# Bluetooth.net
KiCad netlist of a schematic drawn in Altium Designer
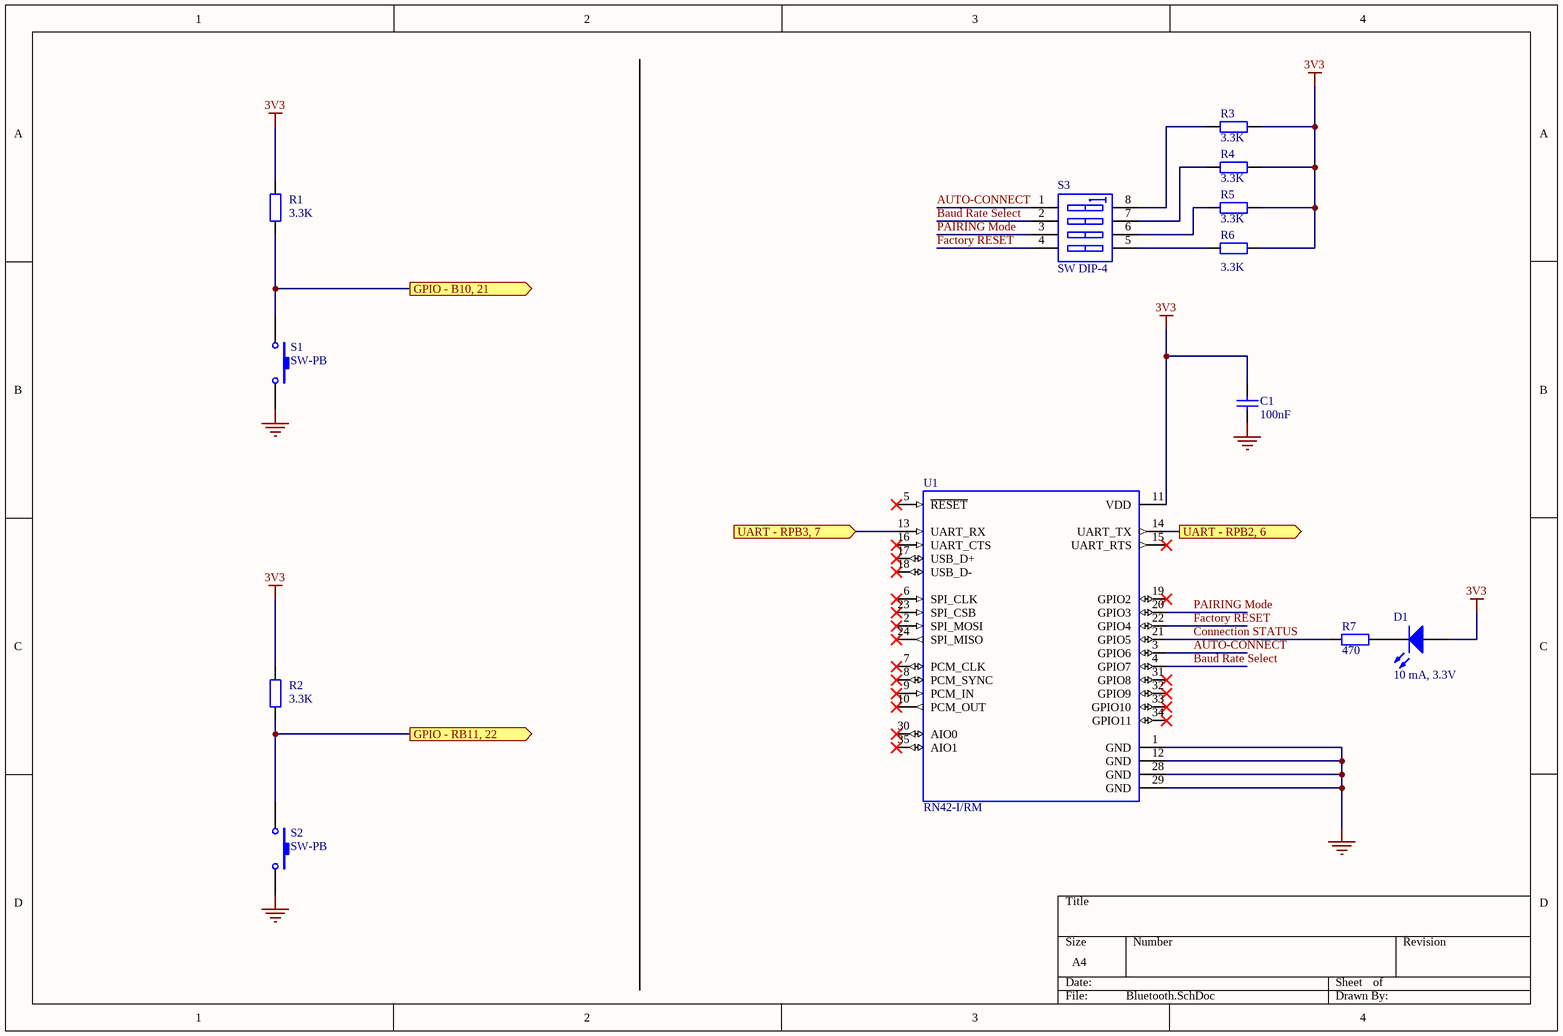
[diagram p0: Bluetooth.SchDoc]

(export (version "E")
  (design (tool "Eeschema 10.0.6"))
  (components
    (comp (ref "C1")
      (value "100nF")
      (footprint "RAD-0.3")
      (description "Capacitor")
      (fields (field (name "PUBLISHER") "Altium Limited"))
      (libsource (lib "Miscellaneous Devices") (part "Cap"))
    )
    (comp (ref "D1")
      (value "10 mA, 3.3V")
      (footprint "LED-0")
      (description "Typical INFRARED GaAs LED")
      (fields (field (name "PUBLISHER") "Altium Limited"))
      (libsource (lib "Miscellaneous Devices") (part "LED0"))
    )
    (comp (ref "R1")
      (value "3.3K")
      (footprint "AXIAL-0.4")
      (description "Resistor")
      (fields (field (name "PUBLISHER") "Altium Limited"))
      (libsource (lib "") (part "Res2_1"))
    )
    (comp (ref "R2")
      (value "3.3K")
      (footprint "AXIAL-0.4")
      (description "Resistor")
      (fields (field (name "PUBLISHER") "Altium Limited"))
      (libsource (lib "") (part "Res2_1"))
    )
    (comp (ref "R3")
      (value "3.3K")
      (footprint "AXIAL-0.4")
      (description "Resistor")
      (fields (field (name "PUBLISHER") "Altium Limited"))
      (libsource (lib "Miscellaneous Devices") (part "Res2"))
    )
    (comp (ref "R4")
      (value "3.3K")
      (footprint "AXIAL-0.4")
      (description "Resistor")
      (fields (field (name "PUBLISHER") "Altium Limited"))
      (libsource (lib "Miscellaneous Devices") (part "Res2"))
    )
    (comp (ref "R5")
      (value "3.3K")
      (footprint "AXIAL-0.4")
      (description "Resistor")
      (fields (field (name "PUBLISHER") "Altium Limited"))
      (libsource (lib "Miscellaneous Devices") (part "Res2"))
    )
    (comp (ref "R6")
      (value "3.3K")
      (footprint "AXIAL-0.4")
      (description "Resistor")
      (fields (field (name "PUBLISHER") "Altium Limited"))
      (libsource (lib "Miscellaneous Devices") (part "Res2"))
    )
    (comp (ref "R7")
      (value "470")
      (footprint "AXIAL-0.4")
      (description "Resistor")
      (fields (field (name "PUBLISHER") "Altium Limited"))
      (libsource (lib "Miscellaneous Devices") (part "Res2"))
    )
    (comp (ref "S1")
      (value "SW-PB")
      (footprint "SPST-2")
      (description "Switch")
      (fields (field (name "PUBLISHER") "Altium Limited"))
      (libsource (lib "Miscellaneous Devices") (part "SW-PB"))
    )
    (comp (ref "S2")
      (value "SW-PB")
      (footprint "SPST-2")
      (description "Switch")
      (fields (field (name "PUBLISHER") "Altium Limited"))
      (libsource (lib "Miscellaneous Devices") (part "SW-PB"))
    )
    (comp (ref "S3")
      (value "SW DIP-4")
      (footprint "SO8_N")
      (description "DIP Switch, 4 Position, SPST")
      (fields (field (name "PUBLISHER") "Altium Limited"))
      (libsource (lib "Miscellaneous Devices") (part "SW DIP-4"))
    )
    (comp (ref "U1")
      (value "RN42-I/RM")
      (footprint "XCVR_RN42-I/RM")
      (description "Bluetooth Module")
      (fields (field (name "MF") "Microchip"))
      (libsource (lib "Schema lib CG") (part "RN42-I/RM"))
    )
  )
  (nets
    (net (code "1") (name "/AUTO-CONNECT") (class "Default")
      (node (ref "S3") (pin "1") (pinfunction "A1_1") (pintype "passive"))
      (node (ref "U1") (pin "3") (pinfunction "GPIO6_3") (pintype "bidirectional"))
    )
    (net (code "2") (name "/Baud Rate Select") (class "Default")
      (node (ref "S3") (pin "2") (pinfunction "A2_2") (pintype "passive"))
      (node (ref "U1") (pin "4") (pinfunction "GPIO7_4") (pintype "bidirectional"))
    )
    (net (code "3") (name "/Connection STATUS") (class "Default")
      (node (ref "R7") (pin "1") (pinfunction "1_1") (pintype "passive"))
      (node (ref "U1") (pin "21") (pinfunction "GPIO5_21") (pintype "bidirectional"))
    )
    (net (code "4") (name "/Factory RESET") (class "Default")
      (node (ref "S3") (pin "4") (pinfunction "A4_4") (pintype "passive"))
      (node (ref "U1") (pin "22") (pinfunction "GPIO4_22") (pintype "bidirectional"))
    )
    (net (code "5") (name "/GPIO - B10, 21") (class "Default")
      (node (ref "R1") (pin "2") (pinfunction "2_2") (pintype "passive"))
      (node (ref "S1") (pin "1") (pinfunction "1_1") (pintype "passive"))
    )
    (net (code "6") (name "/GPIO - RB11, 22") (class "Default")
      (node (ref "R2") (pin "2") (pinfunction "2_2") (pintype "passive"))
      (node (ref "S2") (pin "1") (pinfunction "1_1") (pintype "passive"))
    )
    (net (code "7") (name "/PAIRING Mode") (class "Default")
      (node (ref "S3") (pin "3") (pinfunction "A3_3") (pintype "passive"))
      (node (ref "U1") (pin "20") (pinfunction "GPIO3_20") (pintype "bidirectional"))
    )
    (net (code "8") (name "/UART - RPB2, 6") (class "Default")
      (node (ref "U1") (pin "14") (pinfunction "UART_TX_14") (pintype "output"))
    )
    (net (code "9") (name "/UART - RPB3, 7") (class "Default")
      (node (ref "U1") (pin "13") (pinfunction "UART_RX_13") (pintype "input"))
    )
    (net (code "10") (name "3V3") (class "Default")
      (node (ref "C1") (pin "1") (pinfunction "1_1") (pintype "passive"))
      (node (ref "D1") (pin "1") (pinfunction "A_1") (pintype "passive"))
      (node (ref "R1") (pin "1") (pinfunction "1_1") (pintype "passive"))
      (node (ref "R2") (pin "1") (pinfunction "1_1") (pintype "passive"))
      (node (ref "R3") (pin "2") (pinfunction "2_2") (pintype "passive"))
      (node (ref "R4") (pin "2") (pinfunction "2_2") (pintype "passive"))
      (node (ref "R5") (pin "2") (pinfunction "2_2") (pintype "passive"))
      (node (ref "R6") (pin "2") (pinfunction "2_2") (pintype "passive"))
      (node (ref "U1") (pin "11") (pinfunction "VDD_11") (pintype "power_in"))
    )
    (net (code "11") (name "GND") (class "Default")
      (node (ref "C1") (pin "2") (pinfunction "2_2") (pintype "passive"))
      (node (ref "S1") (pin "2") (pinfunction "2_2") (pintype "passive"))
      (node (ref "S2") (pin "2") (pinfunction "2_2") (pintype "passive"))
      (node (ref "U1") (pin "1") (pinfunction "GND_1") (pintype "power_in"))
      (node (ref "U1") (pin "12") (pinfunction "GND_12") (pintype "power_in"))
      (node (ref "U1") (pin "28") (pinfunction "GND_28") (pintype "power_in"))
      (node (ref "U1") (pin "29") (pinfunction "GND_29") (pintype "power_in"))
    )
    (net (code "12") (name "Net-(D1-K)") (class "Default")
      (node (ref "D1") (pin "2") (pinfunction "K_2") (pintype "passive"))
      (node (ref "R7") (pin "2") (pinfunction "2_2") (pintype "passive"))
    )
    (net (code "13") (name "Net-(S3-B1)") (class "Default")
      (node (ref "R3") (pin "1") (pinfunction "1_1") (pintype "passive"))
      (node (ref "S3") (pin "8") (pinfunction "B1_8") (pintype "passive"))
    )
    (net (code "14") (name "Net-(S3-B2)") (class "Default")
      (node (ref "R4") (pin "1") (pinfunction "1_1") (pintype "passive"))
      (node (ref "S3") (pin "7") (pinfunction "B2_7") (pintype "passive"))
    )
    (net (code "15") (name "Net-(S3-B3)") (class "Default")
      (node (ref "R5") (pin "1") (pinfunction "1_1") (pintype "passive"))
      (node (ref "S3") (pin "6") (pinfunction "B3_6") (pintype "passive"))
    )
    (net (code "16") (name "Net-(S3-B4)") (class "Default")
      (node (ref "R6") (pin "1") (pinfunction "1_1") (pintype "passive"))
      (node (ref "S3") (pin "5") (pinfunction "B4_5") (pintype "passive"))
    )
    (net (code "17") (name "unconnected-(U1-AIO0-Pad30)") (class "Default")
      (node (ref "U1") (pin "30") (pinfunction "AIO0_30") (pintype "bidirectional+no_connect"))
    )
    (net (code "18") (name "unconnected-(U1-AIO1-Pad35)") (class "Default")
      (node (ref "U1") (pin "35") (pinfunction "AIO1_35") (pintype "bidirectional+no_connect"))
    )
    (net (code "19") (name "unconnected-(U1-GPIO2-Pad19)") (class "Default")
      (node (ref "U1") (pin "19") (pinfunction "GPIO2_19") (pintype "bidirectional+no_connect"))
    )
    (net (code "20") (name "unconnected-(U1-GPIO8-Pad31)") (class "Default")
      (node (ref "U1") (pin "31") (pinfunction "GPIO8_31") (pintype "bidirectional+no_connect"))
    )
    (net (code "21") (name "unconnected-(U1-GPIO9-Pad32)") (class "Default")
      (node (ref "U1") (pin "32") (pinfunction "GPIO9_32") (pintype "bidirectional+no_connect"))
    )
    (net (code "22") (name "unconnected-(U1-GPIO10-Pad33)") (class "Default")
      (node (ref "U1") (pin "33") (pinfunction "GPIO10_33") (pintype "bidirectional+no_connect"))
    )
    (net (code "23") (name "unconnected-(U1-GPIO11-Pad34)") (class "Default")
      (node (ref "U1") (pin "34") (pinfunction "GPIO11_34") (pintype "bidirectional+no_connect"))
    )
    (net (code "24") (name "unconnected-(U1-PCM_CLK-Pad7)") (class "Default")
      (node (ref "U1") (pin "7") (pinfunction "PCM_CLK_7") (pintype "bidirectional+no_connect"))
    )
    (net (code "25") (name "unconnected-(U1-PCM_IN-Pad9)") (class "Default")
      (node (ref "U1") (pin "9") (pinfunction "PCM_IN_9") (pintype "input+no_connect"))
    )
    (net (code "26") (name "unconnected-(U1-PCM_OUT-Pad10)") (class "Default")
      (node (ref "U1") (pin "10") (pinfunction "PCM_OUT_10") (pintype "output+no_connect"))
    )
    (net (code "27") (name "unconnected-(U1-PCM_SYNC-Pad8)") (class "Default")
      (node (ref "U1") (pin "8") (pinfunction "PCM_SYNC_8") (pintype "bidirectional+no_connect"))
    )
    (net (code "28") (name "unconnected-(U1-SPI_CLK-Pad6)") (class "Default")
      (node (ref "U1") (pin "6") (pinfunction "SPI_CLK_6") (pintype "input+no_connect"))
    )
    (net (code "29") (name "unconnected-(U1-SPI_CSB-Pad23)") (class "Default")
      (node (ref "U1") (pin "23") (pinfunction "SPI_CSB_23") (pintype "input+no_connect"))
    )
    (net (code "30") (name "unconnected-(U1-SPI_MISO-Pad24)") (class "Default")
      (node (ref "U1") (pin "24") (pinfunction "SPI_MISO_24") (pintype "output+no_connect"))
    )
    (net (code "31") (name "unconnected-(U1-SPI_MOSI-Pad2)") (class "Default")
      (node (ref "U1") (pin "2") (pinfunction "SPI_MOSI_2") (pintype "input+no_connect"))
    )
    (net (code "32") (name "unconnected-(U1-UART_CTS-Pad16)") (class "Default")
      (node (ref "U1") (pin "16") (pinfunction "UART_CTS_16") (pintype "input+no_connect"))
    )
    (net (code "33") (name "unconnected-(U1-UART_RTS-Pad15)") (class "Default")
      (node (ref "U1") (pin "15") (pinfunction "UART_RTS_15") (pintype "output+no_connect"))
    )
    (net (code "34") (name "unconnected-(U1-USB_D+-Pad17)") (class "Default")
      (node (ref "U1") (pin "17") (pinfunction "USB_D+_17") (pintype "bidirectional+no_connect"))
    )
    (net (code "35") (name "unconnected-(U1-USB_D--Pad18)") (class "Default")
      (node (ref "U1") (pin "18") (pinfunction "USB_D-_18") (pintype "bidirectional+no_connect"))
    )
    (net (code "36") (name "unconnected-(U1-~{RESET}-Pad5)") (class "Default")
      (node (ref "U1") (pin "5") (pinfunction "~{RESET}_5") (pintype "input+no_connect"))
    )
  )
)
